# Headers.net
KiCad netlist of a schematic drawn in Altium Designer
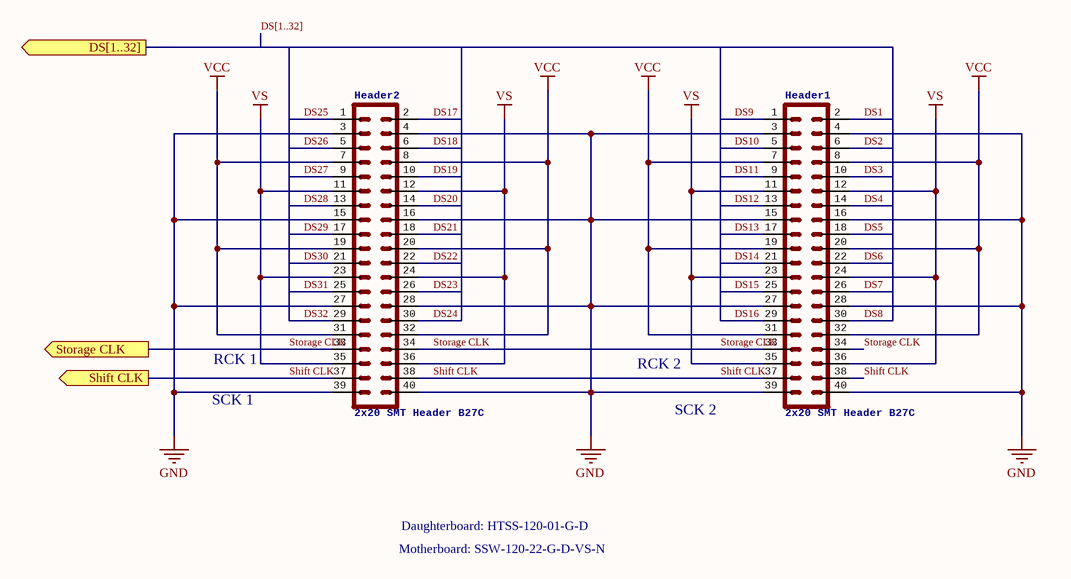
[diagram p0: Headers.SchDoc]

(export (version "E")
  (design (tool "Eeschema 10.0.6"))
  (components
    (comp (ref "Header1")
      (value "2x20 SMT Header B27C")
      (footprint "B27C-SMT2x20")
      (libsource (lib "InteractLab") (part "CONN_20X2SHROUDED_SMT"))
    )
    (comp (ref "Header2")
      (value "2x20 SMT Header B27C")
      (footprint "B27C-SMT2x20")
      (libsource (lib "InteractLab") (part "CONN_20X2SHROUDED_SMT"))
    )
  )
  (nets
    (net (code "1") (name "/DS1") (class "Default")
      (node (ref "Header1") (pin "2") (pinfunction "2_2") (pintype "passive"))
    )
    (net (code "2") (name "/DS2") (class "Default")
      (node (ref "Header1") (pin "6") (pinfunction "6_6") (pintype "passive"))
    )
    (net (code "3") (name "/DS3") (class "Default")
      (node (ref "Header1") (pin "10") (pinfunction "10_10") (pintype "passive"))
    )
    (net (code "4") (name "/DS4") (class "Default")
      (node (ref "Header1") (pin "14") (pinfunction "14_14") (pintype "passive"))
    )
    (net (code "5") (name "/DS5") (class "Default")
      (node (ref "Header1") (pin "18") (pinfunction "18_18") (pintype "passive"))
    )
    (net (code "6") (name "/DS6") (class "Default")
      (node (ref "Header1") (pin "22") (pinfunction "22_22") (pintype "passive"))
    )
    (net (code "7") (name "/DS7") (class "Default")
      (node (ref "Header1") (pin "26") (pinfunction "26_26") (pintype "passive"))
    )
    (net (code "8") (name "/DS8") (class "Default")
      (node (ref "Header1") (pin "30") (pinfunction "30_30") (pintype "passive"))
    )
    (net (code "9") (name "/DS9") (class "Default")
      (node (ref "Header1") (pin "1") (pinfunction "1_1") (pintype "passive"))
    )
    (net (code "10") (name "/DS10") (class "Default")
      (node (ref "Header1") (pin "5") (pinfunction "5_5") (pintype "passive"))
    )
    (net (code "11") (name "/DS11") (class "Default")
      (node (ref "Header1") (pin "9") (pinfunction "9_9") (pintype "passive"))
    )
    (net (code "12") (name "/DS12") (class "Default")
      (node (ref "Header1") (pin "13") (pinfunction "13_13") (pintype "passive"))
    )
    (net (code "13") (name "/DS13") (class "Default")
      (node (ref "Header1") (pin "17") (pinfunction "17_17") (pintype "passive"))
    )
    (net (code "14") (name "/DS14") (class "Default")
      (node (ref "Header1") (pin "21") (pinfunction "21_21") (pintype "passive"))
    )
    (net (code "15") (name "/DS15") (class "Default")
      (node (ref "Header1") (pin "25") (pinfunction "25_25") (pintype "passive"))
    )
    (net (code "16") (name "/DS16") (class "Default")
      (node (ref "Header1") (pin "29") (pinfunction "29_29") (pintype "passive"))
    )
    (net (code "17") (name "/DS17") (class "Default")
      (node (ref "Header2") (pin "2") (pinfunction "2_2") (pintype "passive"))
    )
    (net (code "18") (name "/DS18") (class "Default")
      (node (ref "Header2") (pin "6") (pinfunction "6_6") (pintype "passive"))
    )
    (net (code "19") (name "/DS19") (class "Default")
      (node (ref "Header2") (pin "10") (pinfunction "10_10") (pintype "passive"))
    )
    (net (code "20") (name "/DS20") (class "Default")
      (node (ref "Header2") (pin "14") (pinfunction "14_14") (pintype "passive"))
    )
    (net (code "21") (name "/DS21") (class "Default")
      (node (ref "Header2") (pin "18") (pinfunction "18_18") (pintype "passive"))
    )
    (net (code "22") (name "/DS22") (class "Default")
      (node (ref "Header2") (pin "22") (pinfunction "22_22") (pintype "passive"))
    )
    (net (code "23") (name "/DS23") (class "Default")
      (node (ref "Header2") (pin "26") (pinfunction "26_26") (pintype "passive"))
    )
    (net (code "24") (name "/DS24") (class "Default")
      (node (ref "Header2") (pin "30") (pinfunction "30_30") (pintype "passive"))
    )
    (net (code "25") (name "/DS25") (class "Default")
      (node (ref "Header2") (pin "1") (pinfunction "1_1") (pintype "passive"))
    )
    (net (code "26") (name "/DS26") (class "Default")
      (node (ref "Header2") (pin "5") (pinfunction "5_5") (pintype "passive"))
    )
    (net (code "27") (name "/DS27") (class "Default")
      (node (ref "Header2") (pin "9") (pinfunction "9_9") (pintype "passive"))
    )
    (net (code "28") (name "/DS28") (class "Default")
      (node (ref "Header2") (pin "13") (pinfunction "13_13") (pintype "passive"))
    )
    (net (code "29") (name "/DS29") (class "Default")
      (node (ref "Header2") (pin "17") (pinfunction "17_17") (pintype "passive"))
    )
    (net (code "30") (name "/DS30") (class "Default")
      (node (ref "Header2") (pin "21") (pinfunction "21_21") (pintype "passive"))
    )
    (net (code "31") (name "/DS31") (class "Default")
      (node (ref "Header2") (pin "25") (pinfunction "25_25") (pintype "passive"))
    )
    (net (code "32") (name "/DS32") (class "Default")
      (node (ref "Header2") (pin "29") (pinfunction "29_29") (pintype "passive"))
    )
    (net (code "34") (name "/Shift CLK") (class "Default")
      (node (ref "Header1") (pin "37") (pinfunction "37_37") (pintype "passive"))
      (node (ref "Header1") (pin "38") (pinfunction "38_38") (pintype "passive"))
      (node (ref "Header2") (pin "37") (pinfunction "37_37") (pintype "passive"))
      (node (ref "Header2") (pin "38") (pinfunction "38_38") (pintype "passive"))
    )
    (net (code "35") (name "/Storage CLK") (class "Default")
      (node (ref "Header1") (pin "33") (pinfunction "33_33") (pintype "passive"))
      (node (ref "Header1") (pin "34") (pinfunction "34_34") (pintype "passive"))
      (node (ref "Header2") (pin "33") (pinfunction "33_33") (pintype "passive"))
      (node (ref "Header2") (pin "34") (pinfunction "34_34") (pintype "passive"))
    )
    (net (code "36") (name "GND") (class "Default")
      (node (ref "Header1") (pin "15") (pinfunction "15_15") (pintype "passive"))
      (node (ref "Header1") (pin "16") (pinfunction "16_16") (pintype "passive"))
      (node (ref "Header1") (pin "27") (pinfunction "27_27") (pintype "passive"))
      (node (ref "Header1") (pin "28") (pinfunction "28_28") (pintype "passive"))
      (node (ref "Header1") (pin "3") (pinfunction "3_3") (pintype "passive"))
      (node (ref "Header1") (pin "39") (pinfunction "39_39") (pintype "passive"))
      (node (ref "Header1") (pin "4") (pinfunction "4_4") (pintype "passive"))
      (node (ref "Header1") (pin "40") (pinfunction "40_40") (pintype "passive"))
      (node (ref "Header2") (pin "15") (pinfunction "15_15") (pintype "passive"))
      (node (ref "Header2") (pin "16") (pinfunction "16_16") (pintype "passive"))
      (node (ref "Header2") (pin "27") (pinfunction "27_27") (pintype "passive"))
      (node (ref "Header2") (pin "28") (pinfunction "28_28") (pintype "passive"))
      (node (ref "Header2") (pin "3") (pinfunction "3_3") (pintype "passive"))
      (node (ref "Header2") (pin "39") (pinfunction "39_39") (pintype "passive"))
      (node (ref "Header2") (pin "4") (pinfunction "4_4") (pintype "passive"))
      (node (ref "Header2") (pin "40") (pinfunction "40_40") (pintype "passive"))
    )
    (net (code "37") (name "VCC") (class "Default")
      (node (ref "Header1") (pin "19") (pinfunction "19_19") (pintype "passive"))
      (node (ref "Header1") (pin "20") (pinfunction "20_20") (pintype "passive"))
      (node (ref "Header1") (pin "31") (pinfunction "31_31") (pintype "passive"))
      (node (ref "Header1") (pin "32") (pinfunction "32_32") (pintype "passive"))
      (node (ref "Header1") (pin "7") (pinfunction "7_7") (pintype "passive"))
      (node (ref "Header1") (pin "8") (pinfunction "8_8") (pintype "passive"))
      (node (ref "Header2") (pin "19") (pinfunction "19_19") (pintype "passive"))
      (node (ref "Header2") (pin "20") (pinfunction "20_20") (pintype "passive"))
      (node (ref "Header2") (pin "31") (pinfunction "31_31") (pintype "passive"))
      (node (ref "Header2") (pin "32") (pinfunction "32_32") (pintype "passive"))
      (node (ref "Header2") (pin "7") (pinfunction "7_7") (pintype "passive"))
      (node (ref "Header2") (pin "8") (pinfunction "8_8") (pintype "passive"))
    )
    (net (code "38") (name "VS") (class "Default")
      (node (ref "Header1") (pin "11") (pinfunction "11_11") (pintype "passive"))
      (node (ref "Header1") (pin "12") (pinfunction "12_12") (pintype "passive"))
      (node (ref "Header1") (pin "23") (pinfunction "23_23") (pintype "passive"))
      (node (ref "Header1") (pin "24") (pinfunction "24_24") (pintype "passive"))
      (node (ref "Header1") (pin "35") (pinfunction "35_35") (pintype "passive"))
      (node (ref "Header1") (pin "36") (pinfunction "36_36") (pintype "passive"))
      (node (ref "Header2") (pin "11") (pinfunction "11_11") (pintype "passive"))
      (node (ref "Header2") (pin "12") (pinfunction "12_12") (pintype "passive"))
      (node (ref "Header2") (pin "23") (pinfunction "23_23") (pintype "passive"))
      (node (ref "Header2") (pin "24") (pinfunction "24_24") (pintype "passive"))
      (node (ref "Header2") (pin "35") (pinfunction "35_35") (pintype "passive"))
      (node (ref "Header2") (pin "36") (pinfunction "36_36") (pintype "passive"))
    )
  )
)
